# DAC-Butterworth-LPF.net
KiCad netlist of a schematic drawn in Altium Designer
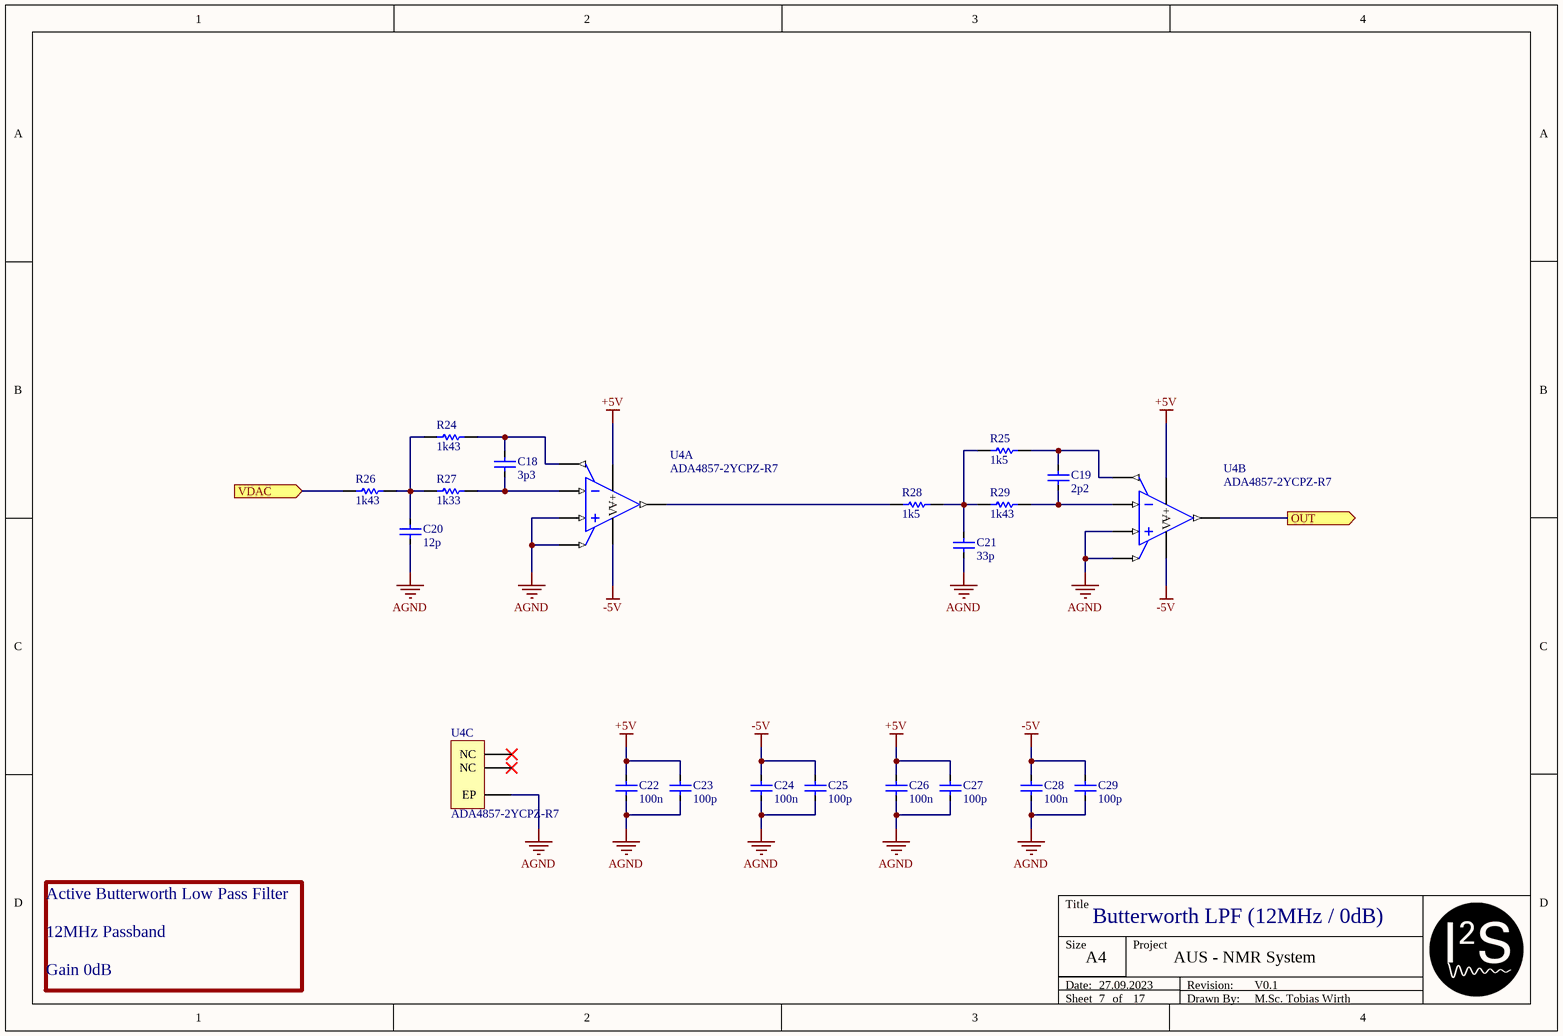
[diagram p0: DAC-Butterworth-LPF.SchDoc]

(export (version "E")
  (design (tool "Eeschema 10.0.6"))
  (components
    (comp (ref "C18") (value "3p3") (footprint "CAP_0402") (libsource (lib "IIS-Lib_TW") (part "Cap")))
    (comp (ref "C19") (value "2p2") (footprint "CAP_0402") (libsource (lib "IIS-Lib_TW") (part "Cap")))
    (comp (ref "C20") (value "12p") (footprint "CAP_0402") (libsource (lib "IIS-Lib_TW") (part "Cap")))
    (comp (ref "C21") (value "33p") (footprint "CAP_0402") (libsource (lib "IIS-Lib_TW") (part "Cap")))
    (comp (ref "C22") (value "100n") (footprint "CAP_0402") (libsource (lib "IIS-Lib_TW") (part "Cap")))
    (comp (ref "C23") (value "100p") (footprint "CAP_0402") (libsource (lib "IIS-Lib_TW") (part "Cap")))
    (comp (ref "C24") (value "100n") (footprint "CAP_0402") (libsource (lib "IIS-Lib_TW") (part "Cap")))
    (comp (ref "C25") (value "100p") (footprint "CAP_0402") (libsource (lib "IIS-Lib_TW") (part "Cap")))
    (comp (ref "C26") (value "100n") (footprint "CAP_0402") (libsource (lib "IIS-Lib_TW") (part "Cap")))
    (comp (ref "C27") (value "100p") (footprint "CAP_0402") (libsource (lib "IIS-Lib_TW") (part "Cap")))
    (comp (ref "C28") (value "100n") (footprint "CAP_0402") (libsource (lib "IIS-Lib_TW") (part "Cap")))
    (comp (ref "C29") (value "100p") (footprint "CAP_0402") (libsource (lib "IIS-Lib_TW") (part "Cap")))
    (comp (ref "R24") (value "1k43") (footprint "RES_0402") (libsource (lib "IIS-Lib_TW") (part "Res")))
    (comp (ref "R25") (value "1k5") (footprint "RES_0402") (libsource (lib "IIS-Lib_TW") (part "Res")))
    (comp (ref "R26") (value "1k43") (footprint "RES_0402") (libsource (lib "IIS-Lib_TW") (part "Res")))
    (comp (ref "R27") (value "1k33") (footprint "RES_0402") (libsource (lib "IIS-Lib_TW") (part "Res")))
    (comp (ref "R28") (value "1k5") (footprint "RES_0402") (libsource (lib "IIS-Lib_TW") (part "Res")))
    (comp (ref "R29") (value "1k43") (footprint "RES_0402") (libsource (lib "IIS-Lib_TW") (part "Res")))
    (comp (ref "U4")
      (value "ADA4857-2YCPZ-R7")
      (footprint "QFN65P400X400X80_HS-17N")
      (fields (field (name "MANUFACTURER") "Analog Devices") (field (name "PARTNUMBER") "ADA4940-2ACPZ-R2"))
      (libsource (lib "IIS-Lib_TW") (part "ADA4857-2"))
    )
  )
  (nets
    (net (code "1") (name "+5V") (class "Default")
      (node (ref "C22") (pin "1") (pinfunction "1_1") (pintype "passive"))
      (node (ref "C23") (pin "1") (pinfunction "1_1") (pintype "passive"))
      (node (ref "C26") (pin "1") (pinfunction "1_1") (pintype "passive"))
      (node (ref "C27") (pin "1") (pinfunction "1_1") (pintype "passive"))
      (node (ref "U4") (pin "14") (pinfunction "V+_14") (pintype "passive"))
      (node (ref "U4") (pin "6") (pinfunction "V+_6") (pintype "passive"))
    )
    (net (code "2") (name "-5V") (class "Default")
      (node (ref "C24") (pin "1") (pinfunction "1_1") (pintype "passive"))
      (node (ref "C25") (pin "1") (pinfunction "1_1") (pintype "passive"))
      (node (ref "C28") (pin "1") (pinfunction "1_1") (pintype "passive"))
      (node (ref "C29") (pin "1") (pinfunction "1_1") (pintype "passive"))
      (node (ref "U4") (pin "12") (pinfunction "V−_12") (pintype "passive"))
      (node (ref "U4") (pin "4") (pinfunction "V−_4") (pintype "passive"))
    )
    (net (code "3") (name "/OUT") (class "Default")
      (node (ref "U4") (pin "5") (pinfunction "OUT2_5") (pintype "output"))
    )
    (net (code "4") (name "/VDAC") (class "Default")
      (node (ref "R26") (pin "1") (pinfunction "1_1") (pintype "passive"))
    )
    (net (code "5") (name "AGND") (class "Default")
      (node (ref "C20") (pin "2") (pinfunction "2_2") (pintype "passive"))
      (node (ref "C21") (pin "2") (pinfunction "2_2") (pintype "passive"))
      (node (ref "C22") (pin "2") (pinfunction "2_2") (pintype "passive"))
      (node (ref "C23") (pin "2") (pinfunction "2_2") (pintype "passive"))
      (node (ref "C24") (pin "2") (pinfunction "2_2") (pintype "passive"))
      (node (ref "C25") (pin "2") (pinfunction "2_2") (pintype "passive"))
      (node (ref "C26") (pin "2") (pinfunction "2_2") (pintype "passive"))
      (node (ref "C27") (pin "2") (pinfunction "2_2") (pintype "passive"))
      (node (ref "C28") (pin "2") (pinfunction "2_2") (pintype "passive"))
      (node (ref "C29") (pin "2") (pinfunction "2_2") (pintype "passive"))
      (node (ref "U4") (pin "10") (pinfunction "IN1+_10") (pintype "input"))
      (node (ref "U4") (pin "15") (pinfunction "PD1_15") (pintype "input"))
      (node (ref "U4") (pin "17") (pinfunction "EP_17") (pintype "power_in"))
      (node (ref "U4") (pin "2") (pinfunction "IN1+_2") (pintype "input"))
      (node (ref "U4") (pin "7") (pinfunction "PD1_7") (pintype "input"))
    )
    (net (code "6") (name "Net-(C20-Pad1)") (class "Default")
      (node (ref "C20") (pin "1") (pinfunction "1_1") (pintype "passive"))
      (node (ref "R24") (pin "1") (pinfunction "1_1") (pintype "passive"))
      (node (ref "R26") (pin "2") (pinfunction "2_2") (pintype "passive"))
      (node (ref "R27") (pin "1") (pinfunction "1_1") (pintype "passive"))
    )
    (net (code "7") (name "Net-(C21-Pad1)") (class "Default")
      (node (ref "C21") (pin "1") (pinfunction "1_1") (pintype "passive"))
      (node (ref "R25") (pin "1") (pinfunction "1_1") (pintype "passive"))
      (node (ref "R28") (pin "2") (pinfunction "2_2") (pintype "passive"))
      (node (ref "R29") (pin "1") (pinfunction "1_1") (pintype "passive"))
    )
    (net (code "8") (name "Net-(U4A-FB1)") (class "Default")
      (node (ref "C18") (pin "1") (pinfunction "1_1") (pintype "passive"))
      (node (ref "R24") (pin "2") (pinfunction "2_2") (pintype "passive"))
      (node (ref "U4") (pin "16") (pinfunction "FB1_16") (pintype "output"))
    )
    (net (code "9") (name "Net-(U4A-IN1-)") (class "Default")
      (node (ref "C18") (pin "2") (pinfunction "2_2") (pintype "passive"))
      (node (ref "R27") (pin "2") (pinfunction "2_2") (pintype "passive"))
      (node (ref "U4") (pin "1") (pinfunction "IN1-_1") (pintype "input"))
    )
    (net (code "10") (name "Net-(U4A-OUT1)") (class "Default")
      (node (ref "R28") (pin "1") (pinfunction "1_1") (pintype "passive"))
      (node (ref "U4") (pin "13") (pinfunction "OUT1_13") (pintype "output"))
    )
    (net (code "11") (name "Net-(U4B-FB2)") (class "Default")
      (node (ref "C19") (pin "1") (pinfunction "1_1") (pintype "passive"))
      (node (ref "R25") (pin "2") (pinfunction "2_2") (pintype "passive"))
      (node (ref "U4") (pin "8") (pinfunction "FB2_8") (pintype "output"))
    )
    (net (code "12") (name "Net-(U4B-IN1-)") (class "Default")
      (node (ref "C19") (pin "2") (pinfunction "2_2") (pintype "passive"))
      (node (ref "R29") (pin "2") (pinfunction "2_2") (pintype "passive"))
      (node (ref "U4") (pin "9") (pinfunction "IN1-_9") (pintype "input"))
    )
    (net (code "13") (name "unconnected-(U4C-NC-Pad3)") (class "Default")
      (node (ref "U4") (pin "3") (pinfunction "NC_3") (pintype "power_in+no_connect"))
    )
    (net (code "14") (name "unconnected-(U4C-NC-Pad11)") (class "Default")
      (node (ref "U4") (pin "11") (pinfunction "NC_11") (pintype "power_in+no_connect"))
    )
  )
)
